# SD_Card.net
KiCad netlist of a schematic drawn in Altium Designer
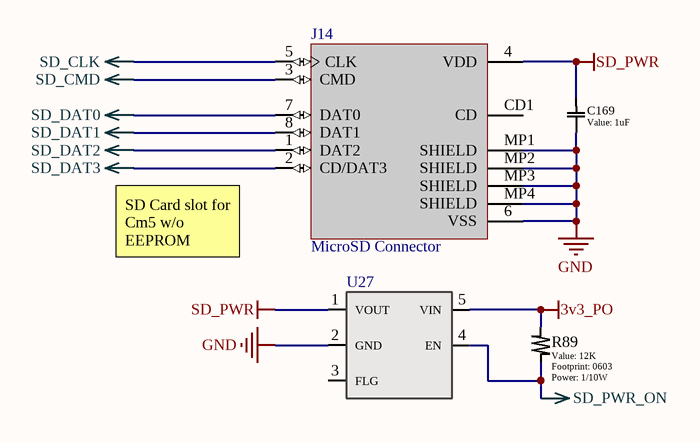
[diagram p0: SD_Card.SchDoc]

(export (version "E")
  (design (tool "Eeschema 10.0.6"))
  (components
    (comp (ref "C169")
      (value "1uF")
      (footprint "0603")
      (fields
        (field (name "VOLTAGE") "6V")
        (field (name "TOLERANCE") "5%")
        (field (name "Comment") "Generic Capacitor")
      )
      (libsource (lib "Capacitors") (part "Generic Capacitor"))
    )
    (comp (ref "J14")
      (value "MicroSD Connector")
      (footprint "TF-01A - NoCut")
      (description "Deck MicroSD card (TF card) Self bomb SMD SD Card Connector")
      (libsource (lib "Connectors") (part "TF-01A"))
    )
    (comp (ref "R89")
      (value "12K")
      (footprint "0603")
      (fields
        (field (name "TOLERANCE") "1%")
        (field (name "POWER") "1/10W")
        (field (name "Comment") "Generic Resistor")
      )
      (libsource (lib "Resistors") (part "Generic Resistor"))
    )
    (comp (ref "U27")
      (value "~")
      (footprint "TSOT-23-5")
      (description "Power Switch/Driver 1:1 N-Channel 1A TSOT-23-5")
      (libsource (lib "Switches") (part "RT9742GGJ5"))
    )
  )
  (nets
    (net (code "1") (name "3v3_PO") (class "Default")
      (node (ref "R89") (pin "1") (pinfunction "1_1") (pintype "passive"))
      (node (ref "U27") (pin "5") (pinfunction "VIN_5") (pintype "passive"))
    )
    (net (code "2") (name "GND") (class "Default")
      (node (ref "C169") (pin "1") (pinfunction "1_1") (pintype "passive"))
      (node (ref "J14") (pin "6") (pinfunction "VSS_6") (pintype "power_in"))
      (node (ref "J14") (pin "MP1") (pinfunction "SHIELD_MP1") (pintype "power_in"))
      (node (ref "J14") (pin "MP2") (pinfunction "SHIELD_MP2") (pintype "power_in"))
      (node (ref "J14") (pin "MP3") (pinfunction "SHIELD_MP3") (pintype "power_in"))
      (node (ref "J14") (pin "MP4") (pinfunction "SHIELD_MP4") (pintype "power_in"))
      (node (ref "U27") (pin "2") (pinfunction "GND_2") (pintype "passive"))
    )
    (net (code "3") (name "SD_CLK") (class "Default")
      (node (ref "J14") (pin "5") (pinfunction "CLK_5") (pintype "bidirectional"))
    )
    (net (code "4") (name "SD_CMD") (class "Default")
      (node (ref "J14") (pin "3") (pinfunction "CMD_3") (pintype "bidirectional"))
    )
    (net (code "5") (name "SD_DAT0") (class "Default")
      (node (ref "J14") (pin "7") (pinfunction "DAT0_7") (pintype "bidirectional"))
    )
    (net (code "6") (name "SD_DAT1") (class "Default")
      (node (ref "J14") (pin "8") (pinfunction "DAT1_8") (pintype "bidirectional"))
    )
    (net (code "7") (name "SD_DAT2") (class "Default")
      (node (ref "J14") (pin "1") (pinfunction "DAT2_1") (pintype "bidirectional"))
    )
    (net (code "8") (name "SD_DAT3") (class "Default")
      (node (ref "J14") (pin "2") (pinfunction "CD/DAT3_2") (pintype "bidirectional"))
    )
    (net (code "9") (name "SD_PWR") (class "Default")
      (node (ref "C169") (pin "2") (pinfunction "2_2") (pintype "passive"))
      (node (ref "J14") (pin "4") (pinfunction "VDD_4") (pintype "power_in"))
      (node (ref "U27") (pin "1") (pinfunction "VOUT_1") (pintype "passive"))
    )
    (net (code "10") (name "SD_PWR_ON") (class "Default")
      (node (ref "R89") (pin "2") (pinfunction "2_2") (pintype "passive"))
      (node (ref "U27") (pin "4") (pinfunction "EN_4") (pintype "passive"))
    )
    (net (code "11") (name "unconnected-(J14-CD-PadCD1)") (class "Default")
      (node (ref "J14") (pin "CD1") (pinfunction "CD_CD1") (pintype "passive"))
    )
    (net (code "12") (name "unconnected-(U27-FLG-Pad3)") (class "Default")
      (node (ref "U27") (pin "3") (pinfunction "FLG_3") (pintype "passive"))
    )
  )
)
